# ISP.net
KiCad netlist of a schematic drawn in Altium Designer
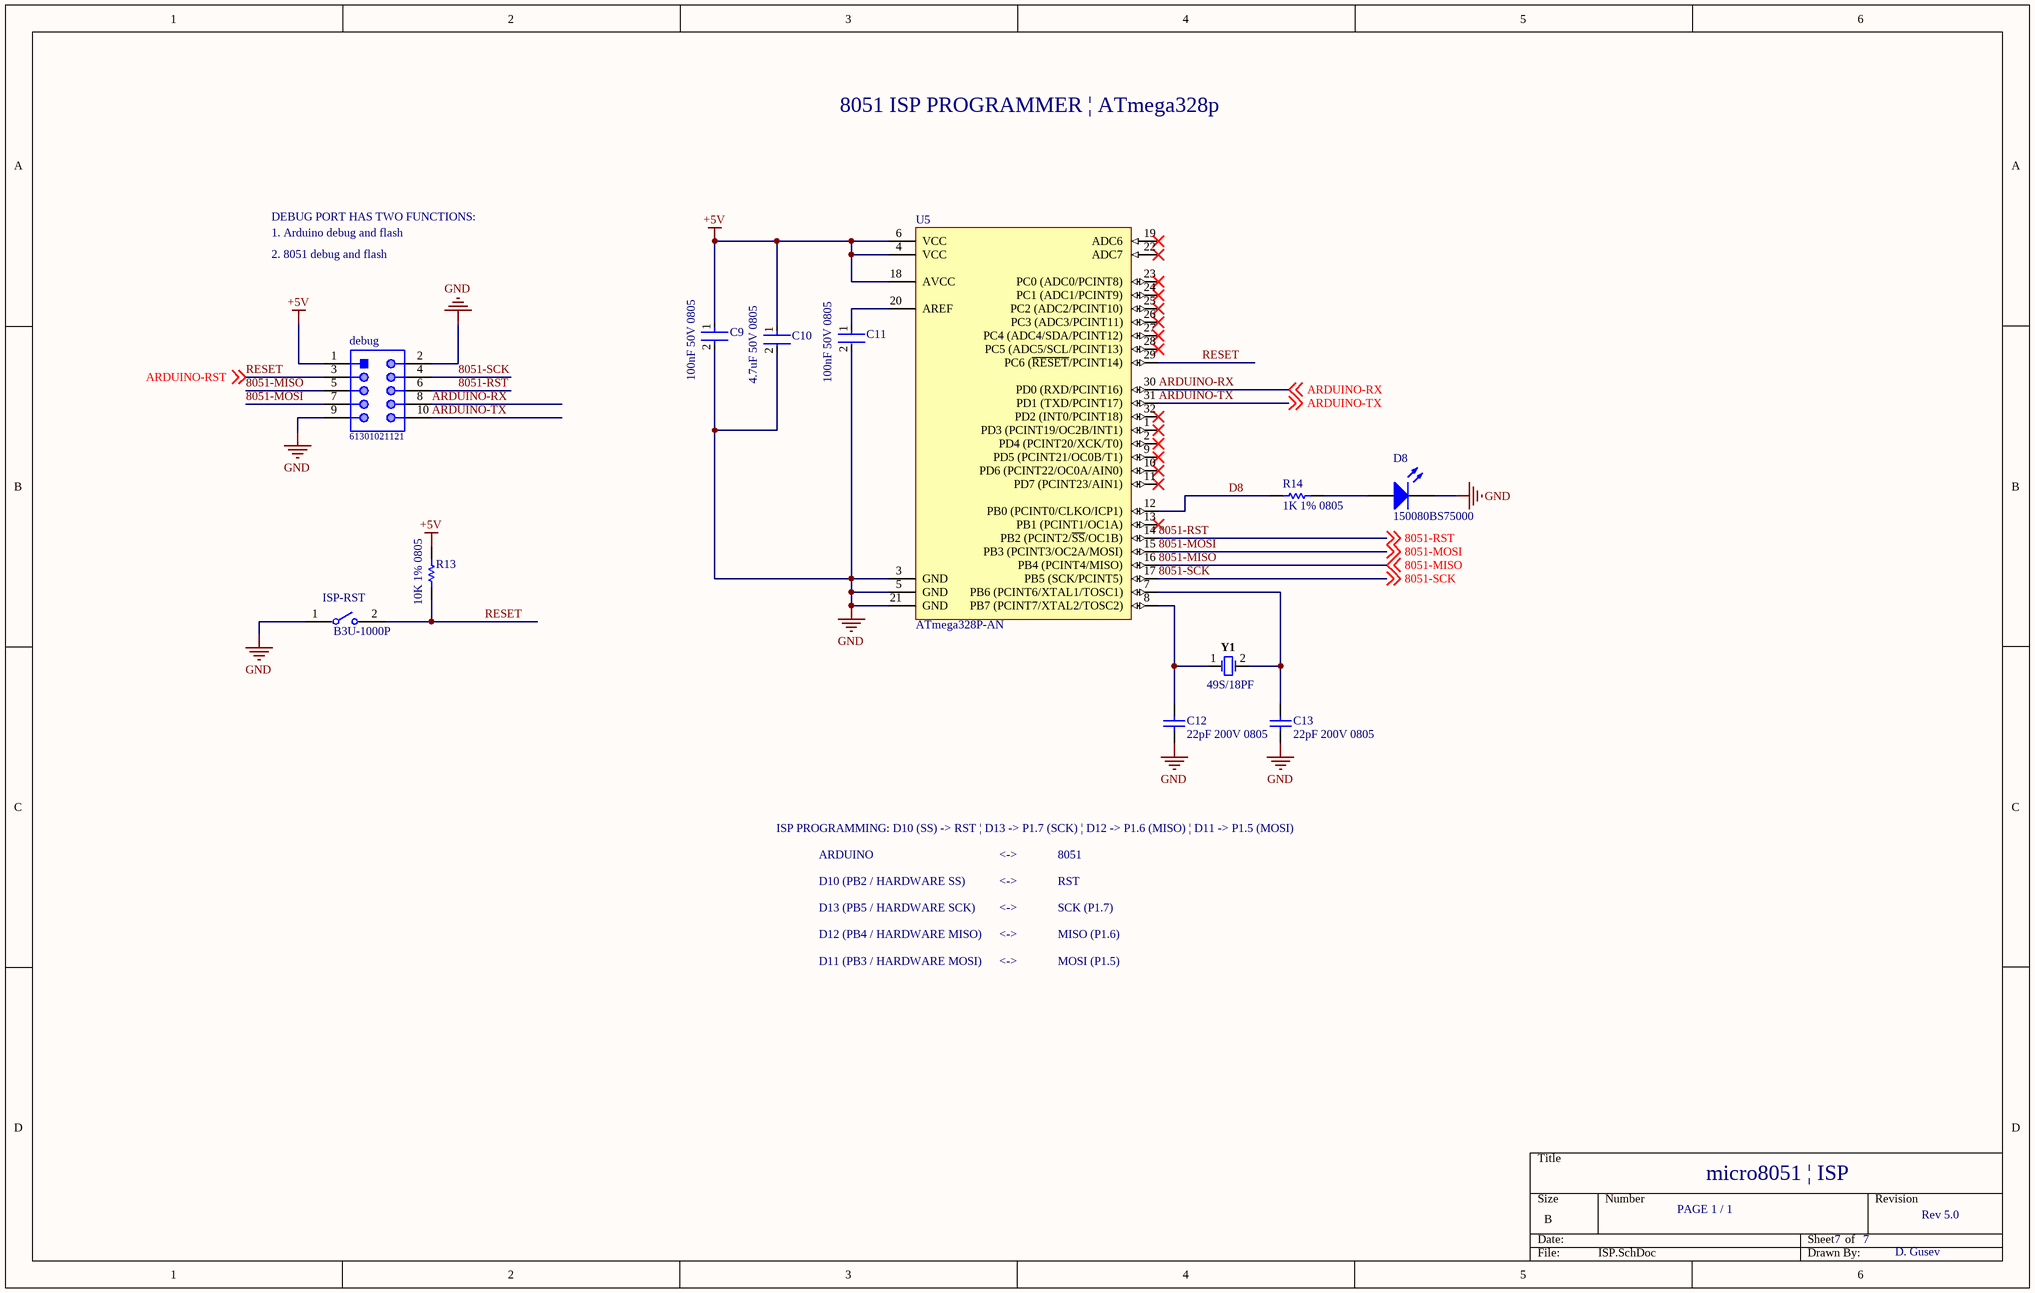
[diagram p0: ISP.SchDoc]

(export (version "E")
  (design (tool "Eeschema 10.0.6"))
  (components
    (comp (ref "C9")
      (value "100nF 50V 0805")
      (footprint "FP-C0805C-DN-MFG")
      (description "CAP CER 0.1UF 50V X7R 0805")
      (fields
        (field (name "MANUFACTURER PART NUMBER") "C0805C104K5RACTU")
        (field (name "MANUFACTURER") "KEMET")
      )
      (libsource (lib "Altium Content Vault") (part "b4654b650e69147ec39a6b967a45e02"))
    )
    (comp (ref "C10")
      (value "4.7uF 50V 0805")
      (footprint "FP-C2012-125-MFG")
      (description "CAP CER 4.7UF 50V X5R 0805")
      (fields
        (field (name "TOLERANCE") "10%")
        (field (name "MANUFACTURER PART NUMBER") "C2012X5R1H475K125AB")
      )
      (libsource (lib "Altium Content Vault") (part "11868f565c42a9108669ba33697ecf6"))
    )
    (comp (ref "C11")
      (value "100nF 50V 0805")
      (footprint "FP-C0805C-DN-MFG")
      (description "CAP CER 0.1UF 50V X7R 0805")
      (fields
        (field (name "MANUFACTURER PART NUMBER") "C0805C104K5RACTU")
        (field (name "MANUFACTURER") "KEMET")
      )
      (libsource (lib "Altium Content Vault") (part "b4654b650e69147ec39a6b967a45e02"))
    )
    (comp (ref "C12")
      (value "22pF 200V 0805")
      (footprint "CAPC2013X115X51NL20T26")
      (fields
        (field (name "MANUFACTURER") "AVX Interconnect / Elco")
        (field (name "PART NUMBER") "08052U220GAT2A")
      )
      (libsource (lib "Altium Content Vault") (part "CAP"))
    )
    (comp (ref "C13")
      (value "22pF 200V 0805")
      (footprint "CAPC2013X115X51NL20T26")
      (fields
        (field (name "MANUFACTURER") "AVX Interconnect / Elco")
        (field (name "PART NUMBER") "08052U220GAT2A")
      )
      (libsource (lib "Altium Content Vault") (part "CAP"))
    )
    (comp (ref "D8")
      (value "150080BS75000")
      (footprint "0805_A")
      (description "SMD mono-color Chip LED, WL-SMCW, Blue")
      (fields (field (name "MANUFACTURER") "Wuerth Elektronik"))
      (libsource (lib "Altium Content Vault") (part "WE-LED_K1A2-2"))
    )
    (comp (ref "debug")
      (value "61301021121")
      (footprint "61301021121")
      (description "THT Vertical Pin Header WR-PHD, Pitch 2.54 mm, Dual Row, 10 pins")
      (fields (field (name "MANUFACTURER") "Wurth Elektronik") (field (name "PUBLISHER") "WurthElektronik"))
      (libsource (lib "Altium Content Vault") (part "WE-CN-2P-M-R10"))
    )
    (comp (ref "ISP-RST")
      (value "B3U-1000P")
      (footprint "FP-B3U-1000P-MFG")
      (description "SWITCH TACTILE SPST-NO 0.05A 12V")
      (libsource (lib "Altium Content Vault") (part "ae622034201233ca1abcedc05908f33"))
    )
    (comp (ref "R13")
      (value "10K 1% 0805")
      (footprint "RESC2013X60X35NL10T20")
      (description "Chip Resistor, 10 KOhm, +/- 1%, 0.125 W, -55 to 155 degC, 0805 (2012 Metric), RoHS, Tape and Reel")
      (fields (field (name "MANUFACTURER") "Yageo"))
      (libsource (lib "Altium Content Vault") (part "RES-2"))
    )
    (comp (ref "R14")
      (value "1K 1% 0805")
      (footprint "RESC2013X60X40ML20T25")
      (fields (field (name "PART NUMBER") "ERA6AEB123V") (field (name "MANUFACTURER") "Panasonic"))
      (libsource (lib "Altium Content Vault") (part "RES"))
    )
    (comp (ref "U5")
      (value "ATmega328P-AN")
      (footprint "32A_N")
      (libsource (lib "Altium Content Vault") (part "MC-8B-ATM48-SQ32"))
    )
    (comp (ref "Y1")
      (value "49S/18PF")
      (footprint "JPY-49S-18PF")
      (description "Crystal, 16 MHz, 18 pF, -20 to 70 degC, 2-Pin THD")
      (fields (field (name "MANUFACTURER") "Shenzhen Jingpengyuan"))
      (libsource (lib "Altium Content Vault") (part "XTAL-1-2-2"))
    )
  )
  (nets
    (net (code "1") (name "+5V") (class "Default")
      (node (ref "C10") (pin "1") (pinfunction "1_1") (pintype "passive"))
      (node (ref "C9") (pin "1") (pinfunction "1_1") (pintype "passive"))
      (node (ref "R13") (pin "2") (pinfunction "2_2") (pintype "passive"))
      (node (ref "U5") (pin "18") (pinfunction "AVCC_18") (pintype "power_in"))
      (node (ref "U5") (pin "4") (pinfunction "VCC_4") (pintype "power_in"))
      (node (ref "U5") (pin "6") (pinfunction "VCC_6") (pintype "power_in"))
      (node (ref "debug") (pin "1") (pinfunction "1_1") (pintype "passive"))
    )
    (net (code "2") (name "/D8") (class "Default")
      (node (ref "R14") (pin "2") (pinfunction "2_2") (pintype "passive"))
      (node (ref "U5") (pin "12") (pinfunction "PB0_(PCINT0/CLKO/ICP1)_12") (pintype "bidirectional"))
    )
    (net (code "3") (name "8051-MISO") (class "Default")
      (node (ref "U5") (pin "16") (pinfunction "PB4_(PCINT4/MISO)_16") (pintype "bidirectional"))
      (node (ref "debug") (pin "5") (pinfunction "5_5") (pintype "passive"))
    )
    (net (code "4") (name "8051-MOSI") (class "Default")
      (node (ref "U5") (pin "15") (pinfunction "PB3_(PCINT3/OC2A/MOSI)_15") (pintype "bidirectional"))
      (node (ref "debug") (pin "7") (pinfunction "7_7") (pintype "passive"))
    )
    (net (code "5") (name "8051-RST") (class "Default")
      (node (ref "U5") (pin "14") (pinfunction "PB2_(PCINT2/~{SS}/OC1B)_14") (pintype "bidirectional"))
      (node (ref "debug") (pin "6") (pinfunction "6_6") (pintype "passive"))
    )
    (net (code "6") (name "8051-SCK") (class "Default")
      (node (ref "U5") (pin "17") (pinfunction "PB5_(SCK/PCINT5)_17") (pintype "bidirectional"))
      (node (ref "debug") (pin "4") (pinfunction "4_4") (pintype "passive"))
    )
    (net (code "7") (name "ARDUINO-RST") (class "Default")
      (node (ref "ISP-RST") (pin "2") (pinfunction "2_2") (pintype "passive"))
      (node (ref "R13") (pin "1") (pinfunction "1_1") (pintype "passive"))
      (node (ref "U5") (pin "29") (pinfunction "PC6_(~{RESET}/PCINT14)_29") (pintype "bidirectional"))
      (node (ref "debug") (pin "3") (pinfunction "3_3") (pintype "passive"))
    )
    (net (code "8") (name "ARDUINO-RX") (class "Default")
      (node (ref "U5") (pin "30") (pinfunction "PD0_(RXD/PCINT16)_30") (pintype "bidirectional"))
      (node (ref "debug") (pin "8") (pinfunction "8_8") (pintype "passive"))
    )
    (net (code "9") (name "ARDUINO-TX") (class "Default")
      (node (ref "U5") (pin "31") (pinfunction "PD1_(TXD/PCINT17)_31") (pintype "bidirectional"))
      (node (ref "debug") (pin "10") (pinfunction "10_10") (pintype "passive"))
    )
    (net (code "10") (name "GND") (class "Default")
      (node (ref "C10") (pin "2") (pinfunction "2_2") (pintype "passive"))
      (node (ref "C11") (pin "2") (pinfunction "2_2") (pintype "passive"))
      (node (ref "C12") (pin "1") (pinfunction "1_1") (pintype "passive"))
      (node (ref "C13") (pin "1") (pinfunction "1_1") (pintype "passive"))
      (node (ref "C9") (pin "2") (pinfunction "2_2") (pintype "passive"))
      (node (ref "D8") (pin "1") (pinfunction "K_1") (pintype "passive"))
      (node (ref "ISP-RST") (pin "1") (pinfunction "1_1") (pintype "passive"))
      (node (ref "U5") (pin "21") (pinfunction "GND_21") (pintype "power_in"))
      (node (ref "U5") (pin "3") (pinfunction "GND_3") (pintype "power_in"))
      (node (ref "U5") (pin "5") (pinfunction "GND_5") (pintype "power_in"))
      (node (ref "debug") (pin "2") (pinfunction "2_2") (pintype "passive"))
      (node (ref "debug") (pin "9") (pinfunction "9_9") (pintype "passive"))
    )
    (net (code "11") (name "Net-(D8-A)") (class "Default")
      (node (ref "D8") (pin "2") (pinfunction "A_2") (pintype "passive"))
      (node (ref "R14") (pin "1") (pinfunction "1_1") (pintype "passive"))
    )
    (net (code "12") (name "Net-(U5-AREF)") (class "Default")
      (node (ref "C11") (pin "1") (pinfunction "1_1") (pintype "passive"))
      (node (ref "U5") (pin "20") (pinfunction "AREF_20") (pintype "passive"))
    )
    (net (code "13") (name "Net-(U5-PB6_(PCINT6{slash}XTAL1{slash}TOSC1))") (class "Default")
      (node (ref "C13") (pin "2") (pinfunction "2_2") (pintype "passive"))
      (node (ref "U5") (pin "7") (pinfunction "PB6_(PCINT6/XTAL1/TOSC1)_7") (pintype "bidirectional"))
      (node (ref "Y1") (pin "2") (pinfunction "2_2") (pintype "passive"))
    )
    (net (code "14") (name "Net-(U5-PB7_(PCINT7{slash}XTAL2{slash}TOSC2))") (class "Default")
      (node (ref "C12") (pin "2") (pinfunction "2_2") (pintype "passive"))
      (node (ref "U5") (pin "8") (pinfunction "PB7_(PCINT7/XTAL2/TOSC2)_8") (pintype "bidirectional"))
      (node (ref "Y1") (pin "1") (pinfunction "1_1") (pintype "passive"))
    )
    (net (code "15") (name "unconnected-(U5-ADC6-Pad19)") (class "Default")
      (node (ref "U5") (pin "19") (pinfunction "ADC6_19") (pintype "input+no_connect"))
    )
    (net (code "16") (name "unconnected-(U5-ADC7-Pad22)") (class "Default")
      (node (ref "U5") (pin "22") (pinfunction "ADC7_22") (pintype "input+no_connect"))
    )
    (net (code "17") (name "unconnected-(U5-PB1_(PCINT1{slash}OC1A)-Pad13)") (class "Default")
      (node (ref "U5") (pin "13") (pinfunction "PB1_(PCINT1/OC1A)_13") (pintype "bidirectional+no_connect"))
    )
    (net (code "18") (name "unconnected-(U5-PC0_(ADC0{slash}PCINT8)-Pad23)") (class "Default")
      (node (ref "U5") (pin "23") (pinfunction "PC0_(ADC0/PCINT8)_23") (pintype "bidirectional+no_connect"))
    )
    (net (code "19") (name "unconnected-(U5-PC1_(ADC1{slash}PCINT9)-Pad24)") (class "Default")
      (node (ref "U5") (pin "24") (pinfunction "PC1_(ADC1/PCINT9)_24") (pintype "bidirectional+no_connect"))
    )
    (net (code "20") (name "unconnected-(U5-PC2_(ADC2{slash}PCINT10)-Pad25)") (class "Default")
      (node (ref "U5") (pin "25") (pinfunction "PC2_(ADC2/PCINT10)_25") (pintype "bidirectional+no_connect"))
    )
    (net (code "21") (name "unconnected-(U5-PC3_(ADC3{slash}PCINT11)-Pad26)") (class "Default")
      (node (ref "U5") (pin "26") (pinfunction "PC3_(ADC3/PCINT11)_26") (pintype "bidirectional+no_connect"))
    )
    (net (code "22") (name "unconnected-(U5-PC4_(ADC4{slash}SDA{slash}PCINT12)-Pad27)") (class "Default")
      (node (ref "U5") (pin "27") (pinfunction "PC4_(ADC4/SDA/PCINT12)_27") (pintype "bidirectional+no_connect"))
    )
    (net (code "23") (name "unconnected-(U5-PC5_(ADC5{slash}SCL{slash}PCINT13)-Pad28)") (class "Default")
      (node (ref "U5") (pin "28") (pinfunction "PC5_(ADC5/SCL/PCINT13)_28") (pintype "bidirectional+no_connect"))
    )
    (net (code "24") (name "unconnected-(U5-PD2_(INT0{slash}PCINT18)-Pad32)") (class "Default")
      (node (ref "U5") (pin "32") (pinfunction "PD2_(INT0/PCINT18)_32") (pintype "bidirectional+no_connect"))
    )
    (net (code "25") (name "unconnected-(U5-PD3_(PCINT19{slash}OC2B{slash}INT1)-Pad1)") (class "Default")
      (node (ref "U5") (pin "1") (pinfunction "PD3_(PCINT19/OC2B/INT1)_1") (pintype "bidirectional+no_connect"))
    )
    (net (code "26") (name "unconnected-(U5-PD4_(PCINT20{slash}XCK{slash}T0)-Pad2)") (class "Default")
      (node (ref "U5") (pin "2") (pinfunction "PD4_(PCINT20/XCK/T0)_2") (pintype "bidirectional+no_connect"))
    )
    (net (code "27") (name "unconnected-(U5-PD5_(PCINT21{slash}OC0B{slash}T1)-Pad9)") (class "Default")
      (node (ref "U5") (pin "9") (pinfunction "PD5_(PCINT21/OC0B/T1)_9") (pintype "bidirectional+no_connect"))
    )
    (net (code "28") (name "unconnected-(U5-PD6_(PCINT22{slash}OC0A{slash}AIN0)-Pad10)") (class "Default")
      (node (ref "U5") (pin "10") (pinfunction "PD6_(PCINT22/OC0A/AIN0)_10") (pintype "bidirectional+no_connect"))
    )
    (net (code "29") (name "unconnected-(U5-PD7_(PCINT23{slash}AIN1)-Pad11)") (class "Default")
      (node (ref "U5") (pin "11") (pinfunction "PD7_(PCINT23/AIN1)_11") (pintype "bidirectional+no_connect"))
    )
  )
)
